# HM-RC-8_Remote-v02a-011.net
KiCad netlist of a schematic drawn in EAGLE
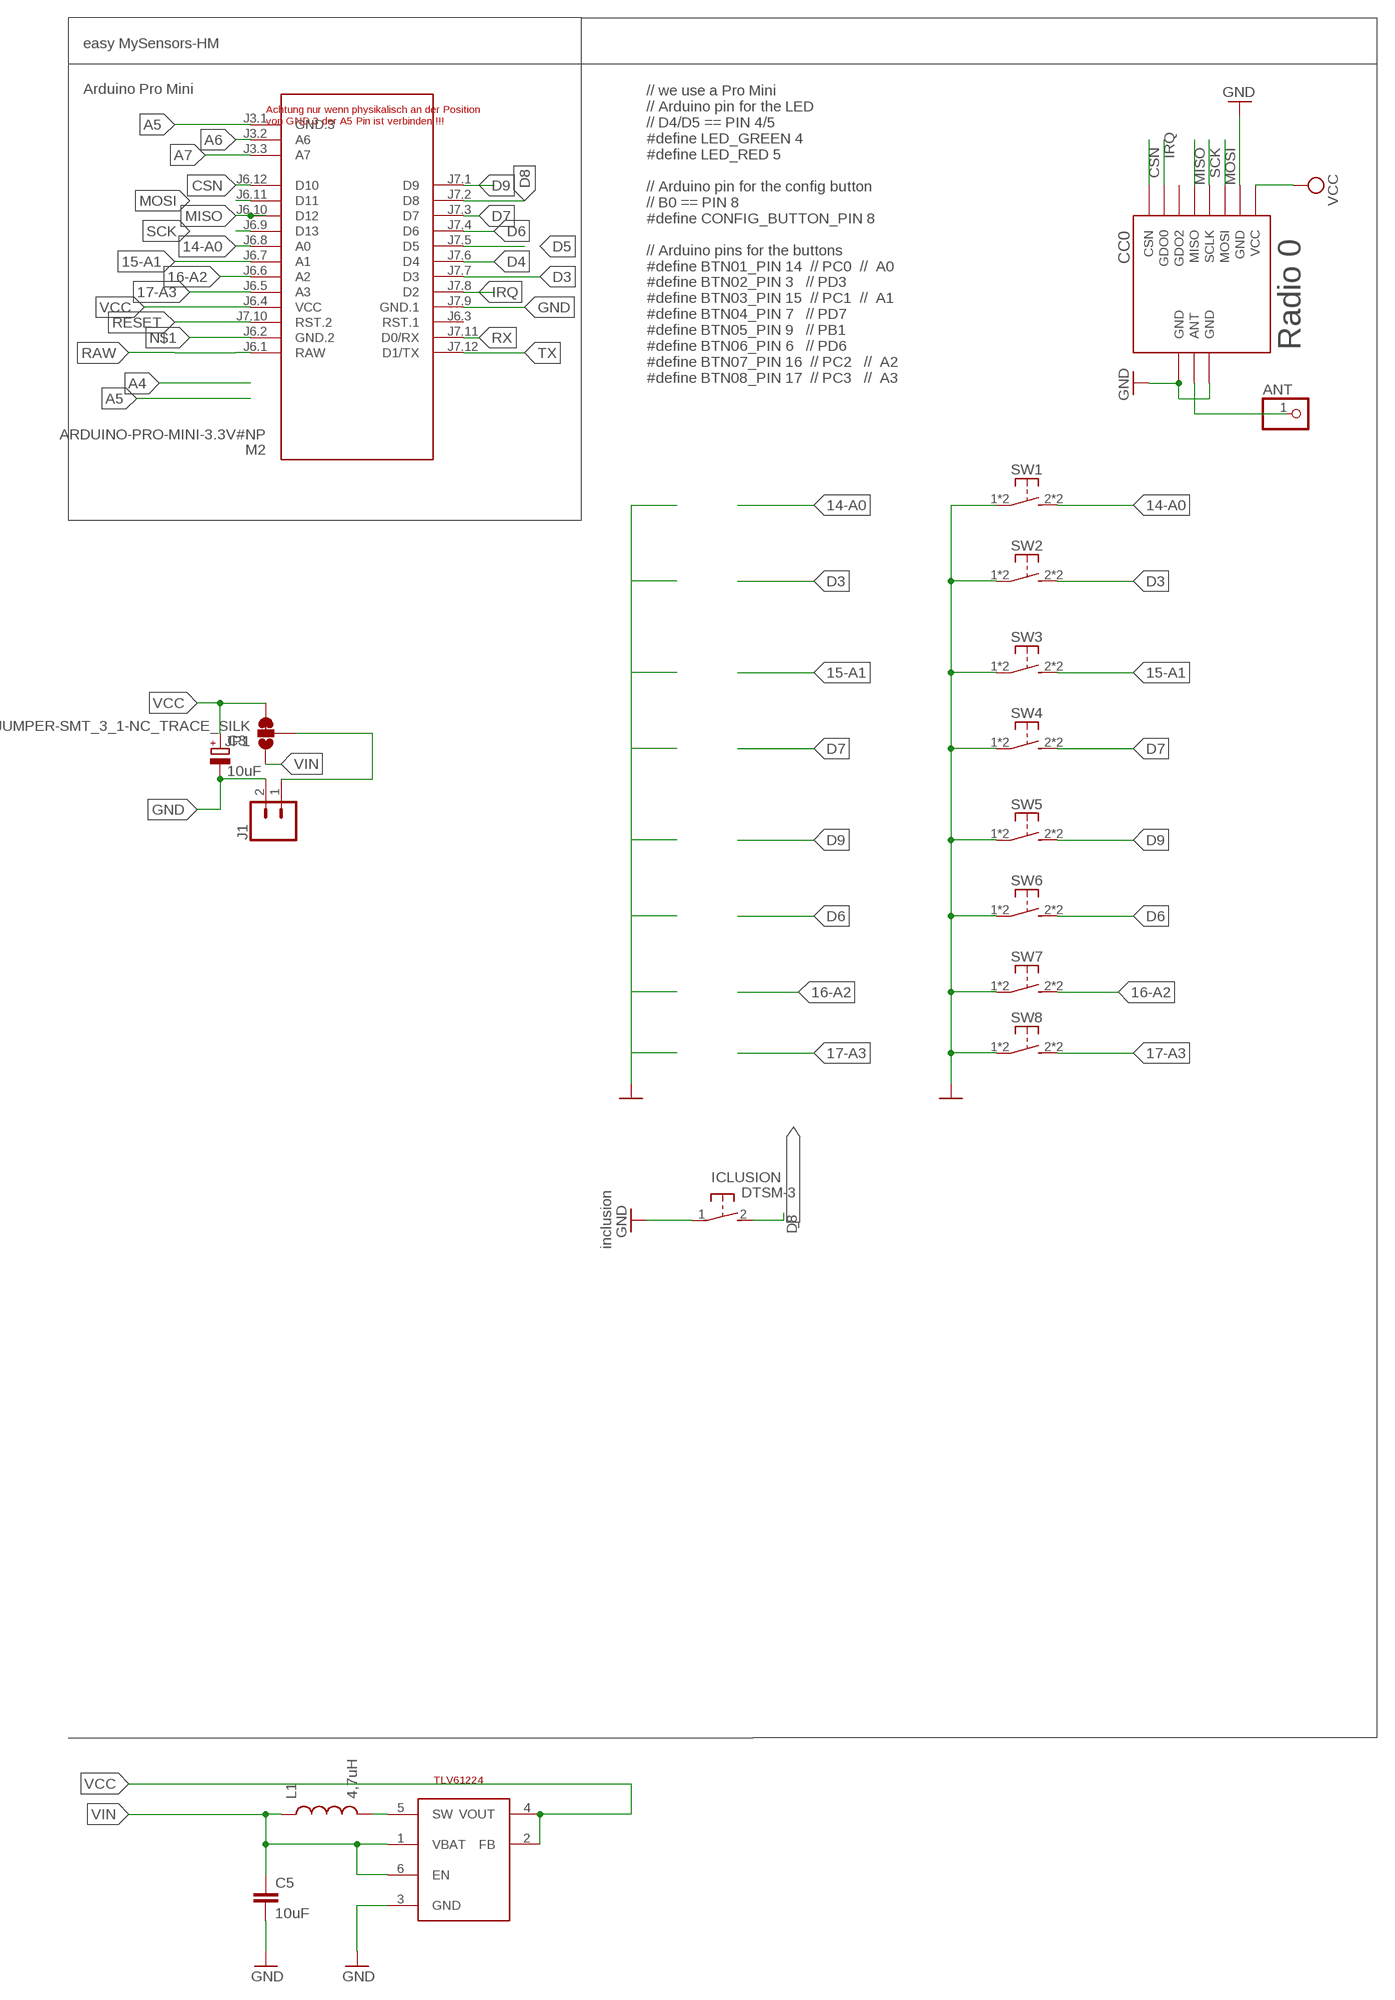
[diagram p0: schematic, sheet 1]

(export (version "E")
  (design (tool "Eeschema 10.0.6"))
  (components
    (comp (ref "ANT")
      (value "PINHD-1X1")
      (footprint "eagle-import:1X01")
      (libsource (lib "eagle-import") (part "PINHD-1X1"))
    )
    (comp (ref "C3")
      (value "10uF")
      (footprint "eagle-import:SMC_C")
      (libsource (lib "eagle-import") (part "CPOL-EUSMCC"))
    )
    (comp (ref "C5")
      (value "10uF")
      (footprint "eagle-import:0805")
      (libsource (lib "eagle-import") (part "CAP0805"))
    )
    (comp (ref "CC0")
      (value "CC1101")
      (footprint "eagle-import:CC1101_MODULE1_SMD")
      (libsource (lib "eagle-import") (part "CC1101_MODULE1SMD"))
    )
    (comp (ref "ICLUSION")
      (value "DTSM-3")
      (footprint "eagle-import:DTSM-3")
      (libsource (lib "eagle-import") (part "DTSM-3"))
    )
    (comp (ref "J1")
      (value "CONN_02PTH3")
      (footprint "eagle-import:1X02_LONGPADS")
      (libsource (lib "eagle-import") (part "CONN_02PTH3"))
    )
    (comp (ref "JP1")
      (value "JUMPER-SMT_3_1-NC_TRACE_SILK")
      (footprint "eagle-import:SMT-JUMPER_3_1-NC_TRACE_SILK")
      (libsource (lib "eagle-import") (part "JUMPER-SMT_3_1-NC_TRACE_SILK"))
    )
    (comp (ref "L1")
      (value "4,7uH")
      (footprint "eagle-import:0805")
      (libsource (lib "eagle-import") (part "INDUCTOR0805"))
    )
    (comp (ref "M2")
      (value "ARDUINO-PRO-MINI-3.3V#NP")
      (footprint "eagle-import:ARDUINO-PRO-MINI#NP")
      (libsource (lib "eagle-import") (part "ARDUINO-PRO-MINI-#NP3.3V"))
    )
    (comp (ref "STEPUP")
      (value "TLV61224")
      (footprint "eagle-import:SOT23-6L")
      (libsource (lib "eagle-import") (part "TI-TLV61224"))
    )
    (comp (ref "SW1")
      (value "SW-TACTILE-TL3305")
      (footprint "eagle-import:TL3305")
      (libsource (lib "eagle-import") (part "SW-TACTILE-TL3305"))
    )
    (comp (ref "SW2")
      (value "SW-TACTILE-TL3305")
      (footprint "eagle-import:TL3305")
      (libsource (lib "eagle-import") (part "SW-TACTILE-TL3305"))
    )
    (comp (ref "SW3")
      (value "SW-TACTILE-TL3305")
      (footprint "eagle-import:TL3305")
      (libsource (lib "eagle-import") (part "SW-TACTILE-TL3305"))
    )
    (comp (ref "SW4")
      (value "SW-TACTILE-TL3305")
      (footprint "eagle-import:TL3305")
      (libsource (lib "eagle-import") (part "SW-TACTILE-TL3305"))
    )
    (comp (ref "SW5")
      (value "SW-TACTILE-TL3305")
      (footprint "eagle-import:TL3305")
      (libsource (lib "eagle-import") (part "SW-TACTILE-TL3305"))
    )
    (comp (ref "SW6")
      (value "SW-TACTILE-TL3305")
      (footprint "eagle-import:TL3305")
      (libsource (lib "eagle-import") (part "SW-TACTILE-TL3305"))
    )
    (comp (ref "SW7")
      (value "SW-TACTILE-TL3305")
      (footprint "eagle-import:TL3305")
      (libsource (lib "eagle-import") (part "SW-TACTILE-TL3305"))
    )
    (comp (ref "SW8")
      (value "SW-TACTILE-TL3305")
      (footprint "eagle-import:TL3305")
      (libsource (lib "eagle-import") (part "SW-TACTILE-TL3305"))
    )
  )
  (nets
    (net (code "1") (name "14-A0") (class "Default")
      (node (ref "M2") (pin "J6.8") (pinfunction "A0_J6.8") (pintype "bidirectional"))
      (node (ref "SW1") (pin "2") (pinfunction "S1_2") (pintype "passive"))
      (node (ref "SW1") (pin "3") (pinfunction "S1_3") (pintype "passive"))
    )
    (net (code "2") (name "15-A1") (class "Default")
      (node (ref "M2") (pin "J6.7") (pinfunction "A1_J6.7") (pintype "bidirectional"))
      (node (ref "SW3") (pin "2") (pinfunction "S1_2") (pintype "passive"))
      (node (ref "SW3") (pin "3") (pinfunction "S1_3") (pintype "passive"))
    )
    (net (code "3") (name "16-A2") (class "Default")
      (node (ref "M2") (pin "J6.6") (pinfunction "A2_J6.6") (pintype "bidirectional"))
      (node (ref "SW7") (pin "2") (pinfunction "S1_2") (pintype "passive"))
      (node (ref "SW7") (pin "3") (pinfunction "S1_3") (pintype "passive"))
    )
    (net (code "4") (name "17-A3") (class "Default")
      (node (ref "M2") (pin "J6.5") (pinfunction "A3_J6.5") (pintype "bidirectional"))
      (node (ref "SW8") (pin "2") (pinfunction "S1_2") (pintype "passive"))
      (node (ref "SW8") (pin "3") (pinfunction "S1_3") (pintype "passive"))
    )
    (net (code "6") (name "A5") (class "Default")
      (node (ref "M2") (pin "J3.1") (pinfunction "GND.3_J3.1") (pintype "bidirectional"))
    )
    (net (code "7") (name "A6") (class "Default")
      (node (ref "M2") (pin "J3.2") (pinfunction "A6_J3.2") (pintype "bidirectional"))
    )
    (net (code "8") (name "A7") (class "Default")
      (node (ref "M2") (pin "J3.3") (pinfunction "A7_J3.3") (pintype "bidirectional"))
    )
    (net (code "9") (name "CSN") (class "Default")
      (node (ref "CC0") (pin "CSN") (pinfunction "CSN_CSN") (pintype "bidirectional"))
      (node (ref "M2") (pin "J6.12") (pinfunction "D10_J6.12") (pintype "bidirectional"))
    )
    (net (code "10") (name "D3") (class "Default")
      (node (ref "M2") (pin "J7.7") (pinfunction "D3_J7.7") (pintype "bidirectional"))
      (node (ref "SW2") (pin "2") (pinfunction "S1_2") (pintype "passive"))
      (node (ref "SW2") (pin "3") (pinfunction "S1_3") (pintype "passive"))
    )
    (net (code "11") (name "D4") (class "Default")
      (node (ref "M2") (pin "J7.6") (pinfunction "D4_J7.6") (pintype "bidirectional"))
    )
    (net (code "12") (name "D5") (class "Default")
      (node (ref "M2") (pin "J7.5") (pinfunction "D5_J7.5") (pintype "bidirectional"))
    )
    (net (code "13") (name "D6") (class "Default")
      (node (ref "M2") (pin "J7.4") (pinfunction "D6_J7.4") (pintype "bidirectional"))
      (node (ref "SW6") (pin "2") (pinfunction "S1_2") (pintype "passive"))
      (node (ref "SW6") (pin "3") (pinfunction "S1_3") (pintype "passive"))
    )
    (net (code "14") (name "D7") (class "Default")
      (node (ref "M2") (pin "J7.3") (pinfunction "D7_J7.3") (pintype "bidirectional"))
      (node (ref "SW4") (pin "2") (pinfunction "S1_2") (pintype "passive"))
      (node (ref "SW4") (pin "3") (pinfunction "S1_3") (pintype "passive"))
    )
    (net (code "15") (name "D8") (class "Default")
      (node (ref "ICLUSION") (pin "2") (pinfunction "2_2") (pintype "passive"))
      (node (ref "M2") (pin "J7.2") (pinfunction "D8_J7.2") (pintype "bidirectional"))
    )
    (net (code "16") (name "D9") (class "Default")
      (node (ref "M2") (pin "J7.1") (pinfunction "D9_J7.1") (pintype "bidirectional"))
      (node (ref "SW5") (pin "2") (pinfunction "S1_2") (pintype "passive"))
      (node (ref "SW5") (pin "3") (pinfunction "S1_3") (pintype "passive"))
    )
    (net (code "17") (name "GND") (class "Default")
      (node (ref "C3") (pin "-") (pinfunction "-_-") (pintype "passive"))
      (node (ref "C5") (pin "2") (pinfunction "2_2") (pintype "passive"))
      (node (ref "CC0") (pin "GND@0") (pinfunction "GND_GND@0") (pintype "power_in"))
      (node (ref "CC0") (pin "GND@1") (pinfunction "GND_GND@1") (pintype "power_in"))
      (node (ref "CC0") (pin "GND@2") (pinfunction "GND_GND@2") (pintype "power_in"))
      (node (ref "ICLUSION") (pin "1") (pinfunction "1_1") (pintype "passive"))
      (node (ref "J1") (pin "2") (pinfunction "2_2") (pintype "passive"))
      (node (ref "M2") (pin "J7.9") (pinfunction "GND.1_J7.9") (pintype "power_in"))
      (node (ref "STEPUP") (pin "3") (pinfunction "GND_3") (pintype "power_in"))
      (node (ref "SW1") (pin "1") (pinfunction "P1_1") (pintype "passive"))
      (node (ref "SW1") (pin "4") (pinfunction "P1_4") (pintype "passive"))
      (node (ref "SW2") (pin "1") (pinfunction "P1_1") (pintype "passive"))
      (node (ref "SW2") (pin "4") (pinfunction "P1_4") (pintype "passive"))
      (node (ref "SW3") (pin "1") (pinfunction "P1_1") (pintype "passive"))
      (node (ref "SW3") (pin "4") (pinfunction "P1_4") (pintype "passive"))
      (node (ref "SW4") (pin "1") (pinfunction "P1_1") (pintype "passive"))
      (node (ref "SW4") (pin "4") (pinfunction "P1_4") (pintype "passive"))
      (node (ref "SW5") (pin "1") (pinfunction "P1_1") (pintype "passive"))
      (node (ref "SW5") (pin "4") (pinfunction "P1_4") (pintype "passive"))
      (node (ref "SW6") (pin "1") (pinfunction "P1_1") (pintype "passive"))
      (node (ref "SW6") (pin "4") (pinfunction "P1_4") (pintype "passive"))
      (node (ref "SW7") (pin "1") (pinfunction "P1_1") (pintype "passive"))
      (node (ref "SW7") (pin "4") (pinfunction "P1_4") (pintype "passive"))
      (node (ref "SW8") (pin "1") (pinfunction "P1_1") (pintype "passive"))
      (node (ref "SW8") (pin "4") (pinfunction "P1_4") (pintype "passive"))
    )
    (net (code "18") (name "IRQ") (class "Default")
      (node (ref "CC0") (pin "GDO0") (pinfunction "GDO0_GDO0") (pintype "bidirectional"))
      (node (ref "M2") (pin "J7.8") (pinfunction "D2_J7.8") (pintype "bidirectional"))
    )
    (net (code "19") (name "MISO") (class "Default")
      (node (ref "CC0") (pin "MISO") (pinfunction "MISO_MISO") (pintype "bidirectional"))
      (node (ref "M2") (pin "J6.10") (pinfunction "D12_J6.10") (pintype "bidirectional"))
    )
    (net (code "20") (name "MOSI") (class "Default")
      (node (ref "CC0") (pin "MOSI") (pinfunction "MOSI_MOSI") (pintype "bidirectional"))
      (node (ref "M2") (pin "J6.11") (pinfunction "D11_J6.11") (pintype "bidirectional"))
    )
    (net (code "21") (name "N$1") (class "Default")
      (node (ref "M2") (pin "J6.2") (pinfunction "GND.2_J6.2") (pintype "power_in"))
    )
    (net (code "22") (name "Net-(ANT-Pad1)") (class "Default")
      (node (ref "ANT") (pin "1") (pinfunction "1_1") (pintype "passive"))
      (node (ref "CC0") (pin "ANT") (pinfunction "ANT_ANT") (pintype "output"))
    )
    (net (code "23") (name "Net-(J1-Pad1)") (class "Default")
      (node (ref "J1") (pin "1") (pinfunction "1_1") (pintype "passive"))
      (node (ref "JP1") (pin "2") (pinfunction "2_2") (pintype "passive"))
    )
    (net (code "24") (name "Net-(STEPUP-SW)") (class "Default")
      (node (ref "L1") (pin "2") (pinfunction "2_2") (pintype "passive"))
      (node (ref "STEPUP") (pin "5") (pinfunction "SW_5") (pintype "power_in"))
    )
    (net (code "25") (name "RAW") (class "Default")
      (node (ref "M2") (pin "J6.1") (pinfunction "RAW_J6.1") (pintype "power_in"))
    )
    (net (code "26") (name "RESET") (class "Default")
      (node (ref "M2") (pin "J7.10") (pinfunction "RST.2_J7.10") (pintype "bidirectional"))
    )
    (net (code "27") (name "RX") (class "Default")
      (node (ref "M2") (pin "J7.11") (pinfunction "D0/RX_J7.11") (pintype "bidirectional"))
    )
    (net (code "28") (name "SCK") (class "Default")
      (node (ref "CC0") (pin "SCLK") (pinfunction "SCLK_SCLK") (pintype "bidirectional"))
      (node (ref "M2") (pin "J6.9") (pinfunction "D13_J6.9") (pintype "bidirectional"))
    )
    (net (code "29") (name "TX") (class "Default")
      (node (ref "M2") (pin "J7.12") (pinfunction "D1/TX_J7.12") (pintype "bidirectional"))
    )
    (net (code "30") (name "VCC") (class "Default")
      (node (ref "C3") (pin "+") (pinfunction "+_+") (pintype "passive"))
      (node (ref "CC0") (pin "VCC") (pinfunction "VCC_VCC") (pintype "power_in"))
      (node (ref "JP1") (pin "3") (pinfunction "3_3") (pintype "passive"))
      (node (ref "M2") (pin "J6.4") (pinfunction "VCC_J6.4") (pintype "power_in"))
      (node (ref "STEPUP") (pin "2") (pinfunction "FB_2") (pintype "input"))
      (node (ref "STEPUP") (pin "4") (pinfunction "VOUT_4") (pintype "power_in"))
    )
    (net (code "31") (name "VIN") (class "Default")
      (node (ref "C5") (pin "1") (pinfunction "1_1") (pintype "passive"))
      (node (ref "JP1") (pin "1") (pinfunction "1_1") (pintype "passive"))
      (node (ref "L1") (pin "1") (pinfunction "1_1") (pintype "passive"))
      (node (ref "STEPUP") (pin "1") (pinfunction "VBAT_1") (pintype "power_in"))
      (node (ref "STEPUP") (pin "6") (pinfunction "EN_6") (pintype "input"))
    )
    (net (code "32") (name "unconnected-(CC0-PadGDO2)") (class "Default")
      (node (ref "CC0") (pin "GDO2") (pinfunction "GDO2_GDO2") (pintype "bidirectional"))
    )
    (net (code "33") (name "unconnected-(M2-RST.1-PadJ6.3)") (class "Default")
      (node (ref "M2") (pin "J6.3") (pinfunction "RST.1_J6.3") (pintype "bidirectional"))
    )
  )
)
